# yyb_v2_5_leds.net
KiCad netlist of a schematic drawn in Altium Designer
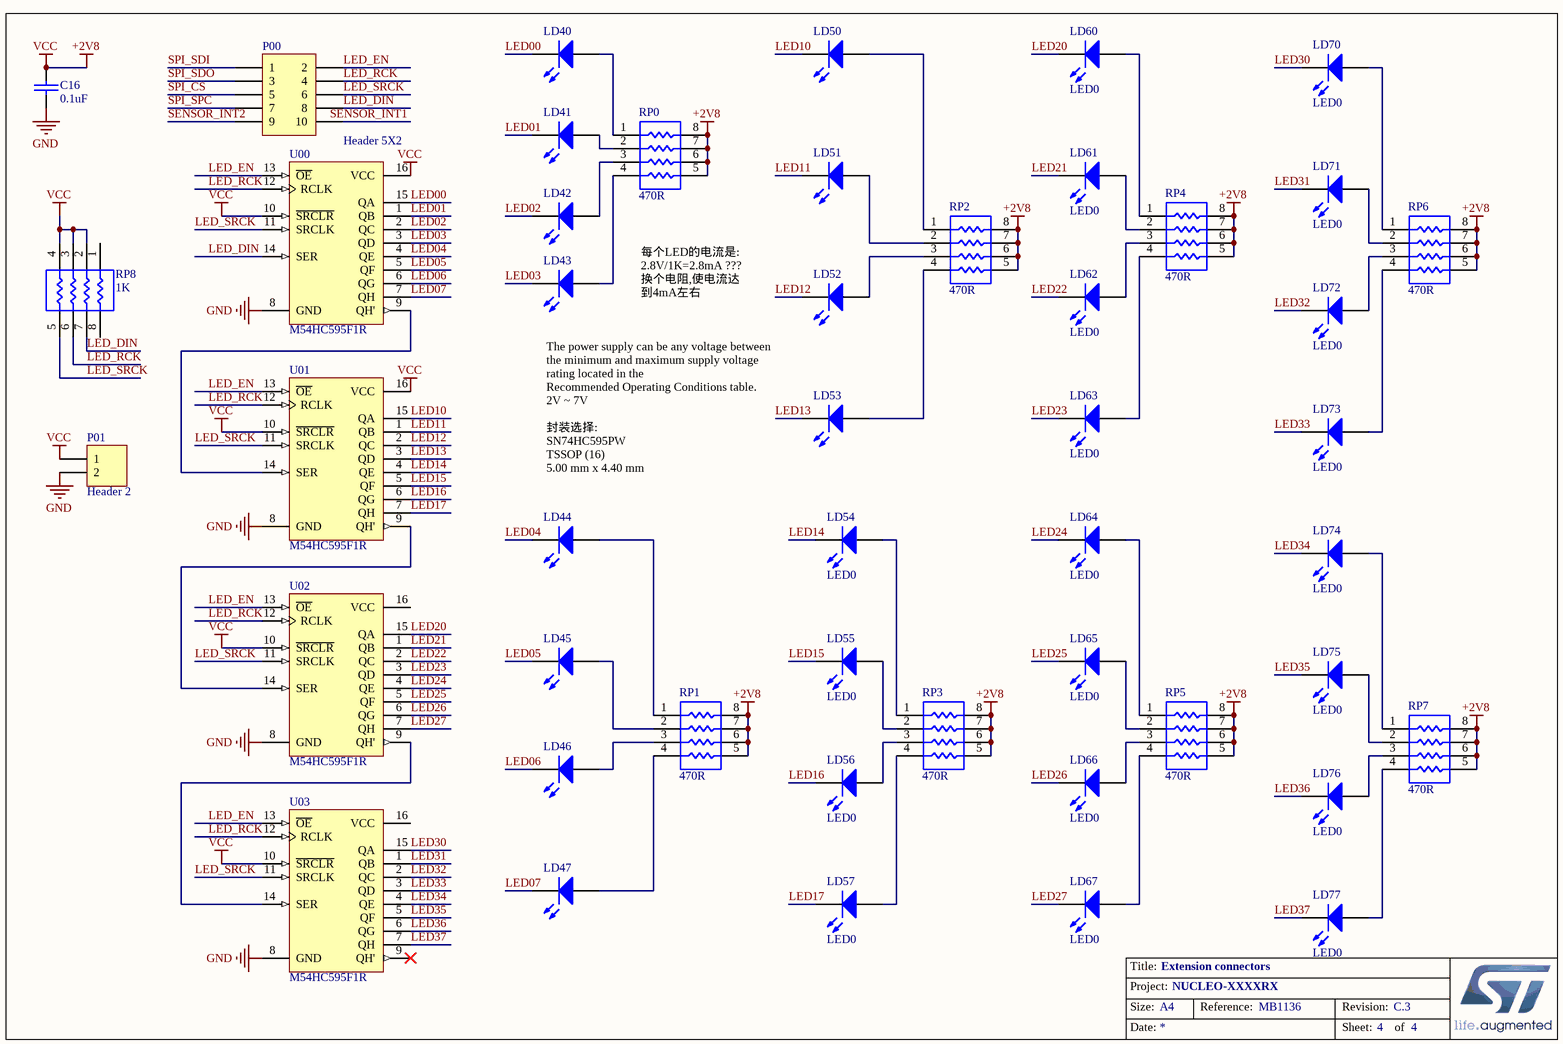
[diagram p0: yyb_v2.5_leds.SchDoc]

(export (version "E")
  (design (tool "Eeschema 10.0.6"))
  (components
    (comp (ref "C16")
      (value "0.1uF")
      (footprint "0603C")
      (description "Capacitor")
      (libsource (lib "*") (part "CAP"))
    )
    (comp (ref "LD40")
      (value "LED0")
      (footprint "LED5")
      (description "Typical INFRARED GaAs LED")
      (fields (field (name "PUBLISHER") "Altium Limited"))
      (libsource (lib "Miscellaneous Devices") (part "LED0"))
    )
    (comp (ref "LD41")
      (value "LED0")
      (footprint "LED5")
      (description "Typical INFRARED GaAs LED")
      (fields (field (name "PUBLISHER") "Altium Limited"))
      (libsource (lib "Miscellaneous Devices") (part "LED0"))
    )
    (comp (ref "LD42")
      (value "LED0")
      (footprint "LED5")
      (description "Typical INFRARED GaAs LED")
      (fields (field (name "PUBLISHER") "Altium Limited"))
      (libsource (lib "Miscellaneous Devices") (part "LED0"))
    )
    (comp (ref "LD43")
      (value "LED0")
      (footprint "LED5")
      (description "Typical INFRARED GaAs LED")
      (fields (field (name "PUBLISHER") "Altium Limited"))
      (libsource (lib "Miscellaneous Devices") (part "LED0"))
    )
    (comp (ref "LD44")
      (value "LED0")
      (footprint "LED5")
      (description "Typical INFRARED GaAs LED")
      (fields (field (name "PUBLISHER") "Altium Limited"))
      (libsource (lib "Miscellaneous Devices") (part "LED0"))
    )
    (comp (ref "LD45")
      (value "LED0")
      (footprint "LED5")
      (description "Typical INFRARED GaAs LED")
      (fields (field (name "PUBLISHER") "Altium Limited"))
      (libsource (lib "Miscellaneous Devices") (part "LED0"))
    )
    (comp (ref "LD46")
      (value "LED0")
      (footprint "LED5")
      (description "Typical INFRARED GaAs LED")
      (fields (field (name "PUBLISHER") "Altium Limited"))
      (libsource (lib "Miscellaneous Devices") (part "LED0"))
    )
    (comp (ref "LD47")
      (value "LED0")
      (footprint "LED5")
      (description "Typical INFRARED GaAs LED")
      (fields (field (name "PUBLISHER") "Altium Limited"))
      (libsource (lib "Miscellaneous Devices") (part "LED0"))
    )
    (comp (ref "LD50")
      (value "LED0")
      (footprint "LED5")
      (description "Typical INFRARED GaAs LED")
      (fields (field (name "PUBLISHER") "Altium Limited"))
      (libsource (lib "Miscellaneous Devices") (part "LED0"))
    )
    (comp (ref "LD51")
      (value "LED0")
      (footprint "LED5")
      (description "Typical INFRARED GaAs LED")
      (fields (field (name "PUBLISHER") "Altium Limited"))
      (libsource (lib "Miscellaneous Devices") (part "LED0"))
    )
    (comp (ref "LD52")
      (value "LED0")
      (footprint "LED5")
      (description "Typical INFRARED GaAs LED")
      (fields (field (name "PUBLISHER") "Altium Limited"))
      (libsource (lib "Miscellaneous Devices") (part "LED0"))
    )
    (comp (ref "LD53")
      (value "LED0")
      (footprint "LED5")
      (description "Typical INFRARED GaAs LED")
      (fields (field (name "PUBLISHER") "Altium Limited"))
      (libsource (lib "Miscellaneous Devices") (part "LED0"))
    )
    (comp (ref "LD54")
      (value "LED0")
      (footprint "LED5")
      (description "Typical INFRARED GaAs LED")
      (fields (field (name "PUBLISHER") "Altium Limited"))
      (libsource (lib "Miscellaneous Devices") (part "LED0"))
    )
    (comp (ref "LD55")
      (value "LED0")
      (footprint "LED5")
      (description "Typical INFRARED GaAs LED")
      (fields (field (name "PUBLISHER") "Altium Limited"))
      (libsource (lib "Miscellaneous Devices") (part "LED0"))
    )
    (comp (ref "LD56")
      (value "LED0")
      (footprint "LED5")
      (description "Typical INFRARED GaAs LED")
      (fields (field (name "PUBLISHER") "Altium Limited"))
      (libsource (lib "Miscellaneous Devices") (part "LED0"))
    )
    (comp (ref "LD57")
      (value "LED0")
      (footprint "LED5")
      (description "Typical INFRARED GaAs LED")
      (fields (field (name "PUBLISHER") "Altium Limited"))
      (libsource (lib "Miscellaneous Devices") (part "LED0"))
    )
    (comp (ref "LD60")
      (value "LED0")
      (footprint "LED5")
      (description "Typical INFRARED GaAs LED")
      (fields (field (name "PUBLISHER") "Altium Limited"))
      (libsource (lib "Miscellaneous Devices") (part "LED0"))
    )
    (comp (ref "LD61")
      (value "LED0")
      (footprint "LED5")
      (description "Typical INFRARED GaAs LED")
      (fields (field (name "PUBLISHER") "Altium Limited"))
      (libsource (lib "Miscellaneous Devices") (part "LED0"))
    )
    (comp (ref "LD62")
      (value "LED0")
      (footprint "LED5")
      (description "Typical INFRARED GaAs LED")
      (fields (field (name "PUBLISHER") "Altium Limited"))
      (libsource (lib "Miscellaneous Devices") (part "LED0"))
    )
    (comp (ref "LD63")
      (value "LED0")
      (footprint "LED5")
      (description "Typical INFRARED GaAs LED")
      (fields (field (name "PUBLISHER") "Altium Limited"))
      (libsource (lib "Miscellaneous Devices") (part "LED0"))
    )
    (comp (ref "LD64")
      (value "LED0")
      (footprint "LED5")
      (description "Typical INFRARED GaAs LED")
      (fields (field (name "PUBLISHER") "Altium Limited"))
      (libsource (lib "Miscellaneous Devices") (part "LED0"))
    )
    (comp (ref "LD65")
      (value "LED0")
      (footprint "LED5")
      (description "Typical INFRARED GaAs LED")
      (fields (field (name "PUBLISHER") "Altium Limited"))
      (libsource (lib "Miscellaneous Devices") (part "LED0"))
    )
    (comp (ref "LD66")
      (value "LED0")
      (footprint "LED5")
      (description "Typical INFRARED GaAs LED")
      (fields (field (name "PUBLISHER") "Altium Limited"))
      (libsource (lib "Miscellaneous Devices") (part "LED0"))
    )
    (comp (ref "LD67")
      (value "LED0")
      (footprint "LED5")
      (description "Typical INFRARED GaAs LED")
      (fields (field (name "PUBLISHER") "Altium Limited"))
      (libsource (lib "Miscellaneous Devices") (part "LED0"))
    )
    (comp (ref "LD70")
      (value "LED0")
      (footprint "LED5")
      (description "Typical INFRARED GaAs LED")
      (fields (field (name "PUBLISHER") "Altium Limited"))
      (libsource (lib "Miscellaneous Devices") (part "LED0"))
    )
    (comp (ref "LD71")
      (value "LED0")
      (footprint "LED5")
      (description "Typical INFRARED GaAs LED")
      (fields (field (name "PUBLISHER") "Altium Limited"))
      (libsource (lib "Miscellaneous Devices") (part "LED0"))
    )
    (comp (ref "LD72")
      (value "LED0")
      (footprint "LED5")
      (description "Typical INFRARED GaAs LED")
      (fields (field (name "PUBLISHER") "Altium Limited"))
      (libsource (lib "Miscellaneous Devices") (part "LED0"))
    )
    (comp (ref "LD73")
      (value "LED0")
      (footprint "LED5")
      (description "Typical INFRARED GaAs LED")
      (fields (field (name "PUBLISHER") "Altium Limited"))
      (libsource (lib "Miscellaneous Devices") (part "LED0"))
    )
    (comp (ref "LD74")
      (value "LED0")
      (footprint "LED5")
      (description "Typical INFRARED GaAs LED")
      (fields (field (name "PUBLISHER") "Altium Limited"))
      (libsource (lib "Miscellaneous Devices") (part "LED0"))
    )
    (comp (ref "LD75")
      (value "LED0")
      (footprint "LED5")
      (description "Typical INFRARED GaAs LED")
      (fields (field (name "PUBLISHER") "Altium Limited"))
      (libsource (lib "Miscellaneous Devices") (part "LED0"))
    )
    (comp (ref "LD76")
      (value "LED0")
      (footprint "LED5")
      (description "Typical INFRARED GaAs LED")
      (fields (field (name "PUBLISHER") "Altium Limited"))
      (libsource (lib "Miscellaneous Devices") (part "LED0"))
    )
    (comp (ref "LD77")
      (value "LED0")
      (footprint "LED5")
      (description "Typical INFRARED GaAs LED")
      (fields (field (name "PUBLISHER") "Altium Limited"))
      (libsource (lib "Miscellaneous Devices") (part "LED0"))
    )
    (comp (ref "P00")
      (value "Header 5X2")
      (footprint "HDR2X5")
      (description "Header, 5-Pin, Dual row")
      (fields (field (name "PUBLISHER") "Altium Limited"))
      (libsource (lib "Miscellaneous Connectors") (part "Header 5X2"))
    )
    (comp (ref "P01")
      (value "Header 2")
      (footprint "HDR1X2")
      (description "Header, 2-Pin")
      (fields (field (name "PUBLISHER") "Altium Limited"))
      (libsource (lib "Miscellaneous Connectors") (part "Header 2"))
    )
    (comp (ref "RP0") (value "470R") (footprint "4P8") (libsource (lib "*") (part "RESPACK3_1")))
    (comp (ref "RP1") (value "470R") (footprint "4P8") (libsource (lib "*") (part "RESPACK3_1")))
    (comp (ref "RP2") (value "470R") (footprint "4P8") (libsource (lib "*") (part "RESPACK3_1")))
    (comp (ref "RP3") (value "470R") (footprint "4P8") (libsource (lib "*") (part "RESPACK3_1")))
    (comp (ref "RP4") (value "470R") (footprint "4P8") (libsource (lib "*") (part "RESPACK3_1")))
    (comp (ref "RP5") (value "470R") (footprint "4P8") (libsource (lib "*") (part "RESPACK3_1")))
    (comp (ref "RP6") (value "470R") (footprint "4P8") (libsource (lib "*") (part "RESPACK3_1")))
    (comp (ref "RP7") (value "470R") (footprint "4P8") (libsource (lib "*") (part "RESPACK3_1")))
    (comp (ref "RP8") (value "1K") (footprint "4P8") (libsource (lib "*") (part "RESPACK3_1")))
    (comp (ref "U00")
      (value "M54HC595F1R")
      (footprint "DIP16")
      (description "8 Bit Shift Register with Output Latches (3 STATE)")
      (fields (field (name "PUBLISHER") "Altium Limited"))
      (libsource (lib "ST Logic Register") (part "M54HC595F1R"))
    )
    (comp (ref "U01")
      (value "M54HC595F1R")
      (footprint "DIP16")
      (description "8 Bit Shift Register with Output Latches (3 STATE)")
      (fields (field (name "PUBLISHER") "Altium Limited"))
      (libsource (lib "ST Logic Register") (part "M54HC595F1R"))
    )
    (comp (ref "U02")
      (value "M54HC595F1R")
      (footprint "DIP16")
      (description "8 Bit Shift Register with Output Latches (3 STATE)")
      (fields (field (name "PUBLISHER") "Altium Limited"))
      (libsource (lib "ST Logic Register") (part "M54HC595F1R"))
    )
    (comp (ref "U03")
      (value "M54HC595F1R")
      (footprint "DIP16")
      (description "8 Bit Shift Register with Output Latches (3 STATE)")
      (fields (field (name "PUBLISHER") "Altium Limited"))
      (libsource (lib "ST Logic Register") (part "M54HC595F1R"))
    )
  )
  (nets
    (net (code "1") (name "+2V8") (class "Default")
      (node (ref "C16") (pin "1") (pinfunction "1_1") (pintype "passive"))
      (node (ref "P01") (pin "1") (pinfunction "1_1") (pintype "passive"))
      (node (ref "RP0") (pin "5") (pinfunction "5_5") (pintype "passive"))
      (node (ref "RP0") (pin "6") (pinfunction "6_6") (pintype "passive"))
      (node (ref "RP0") (pin "7") (pinfunction "7_7") (pintype "passive"))
      (node (ref "RP0") (pin "8") (pinfunction "8_8") (pintype "passive"))
      (node (ref "RP1") (pin "5") (pinfunction "5_5") (pintype "passive"))
      (node (ref "RP1") (pin "6") (pinfunction "6_6") (pintype "passive"))
      (node (ref "RP1") (pin "7") (pinfunction "7_7") (pintype "passive"))
      (node (ref "RP1") (pin "8") (pinfunction "8_8") (pintype "passive"))
      (node (ref "RP2") (pin "5") (pinfunction "5_5") (pintype "passive"))
      (node (ref "RP2") (pin "6") (pinfunction "6_6") (pintype "passive"))
      (node (ref "RP2") (pin "7") (pinfunction "7_7") (pintype "passive"))
      (node (ref "RP2") (pin "8") (pinfunction "8_8") (pintype "passive"))
      (node (ref "RP3") (pin "5") (pinfunction "5_5") (pintype "passive"))
      (node (ref "RP3") (pin "6") (pinfunction "6_6") (pintype "passive"))
      (node (ref "RP3") (pin "7") (pinfunction "7_7") (pintype "passive"))
      (node (ref "RP3") (pin "8") (pinfunction "8_8") (pintype "passive"))
      (node (ref "RP4") (pin "5") (pinfunction "5_5") (pintype "passive"))
      (node (ref "RP4") (pin "6") (pinfunction "6_6") (pintype "passive"))
      (node (ref "RP4") (pin "7") (pinfunction "7_7") (pintype "passive"))
      (node (ref "RP4") (pin "8") (pinfunction "8_8") (pintype "passive"))
      (node (ref "RP5") (pin "5") (pinfunction "5_5") (pintype "passive"))
      (node (ref "RP5") (pin "6") (pinfunction "6_6") (pintype "passive"))
      (node (ref "RP5") (pin "7") (pinfunction "7_7") (pintype "passive"))
      (node (ref "RP5") (pin "8") (pinfunction "8_8") (pintype "passive"))
      (node (ref "RP6") (pin "5") (pinfunction "5_5") (pintype "passive"))
      (node (ref "RP6") (pin "6") (pinfunction "6_6") (pintype "passive"))
      (node (ref "RP6") (pin "7") (pinfunction "7_7") (pintype "passive"))
      (node (ref "RP6") (pin "8") (pinfunction "8_8") (pintype "passive"))
      (node (ref "RP7") (pin "5") (pinfunction "5_5") (pintype "passive"))
      (node (ref "RP7") (pin "6") (pinfunction "6_6") (pintype "passive"))
      (node (ref "RP7") (pin "7") (pinfunction "7_7") (pintype "passive"))
      (node (ref "RP7") (pin "8") (pinfunction "8_8") (pintype "passive"))
      (node (ref "RP8") (pin "2") (pinfunction "2_2") (pintype "passive"))
      (node (ref "RP8") (pin "3") (pinfunction "3_3") (pintype "passive"))
      (node (ref "RP8") (pin "4") (pinfunction "4_4") (pintype "passive"))
      (node (ref "U00") (pin "10") (pinfunction "~{SRCLR}_10") (pintype "input"))
      (node (ref "U00") (pin "16") (pinfunction "VCC_16") (pintype "power_in"))
      (node (ref "U01") (pin "10") (pinfunction "~{SRCLR}_10") (pintype "input"))
      (node (ref "U01") (pin "16") (pinfunction "VCC_16") (pintype "power_in"))
      (node (ref "U02") (pin "10") (pinfunction "~{SRCLR}_10") (pintype "input"))
      (node (ref "U03") (pin "10") (pinfunction "~{SRCLR}_10") (pintype "input"))
    )
    (net (code "2") (name "/LED00") (class "Default")
      (node (ref "LD40") (pin "2") (pinfunction "K_2") (pintype "passive"))
      (node (ref "U00") (pin "15") (pinfunction "QA_15") (pintype "tri_state"))
    )
    (net (code "3") (name "/LED01") (class "Default")
      (node (ref "LD41") (pin "2") (pinfunction "K_2") (pintype "passive"))
      (node (ref "U00") (pin "1") (pinfunction "QB_1") (pintype "tri_state"))
    )
    (net (code "4") (name "/LED02") (class "Default")
      (node (ref "LD42") (pin "2") (pinfunction "K_2") (pintype "passive"))
      (node (ref "U00") (pin "2") (pinfunction "QC_2") (pintype "tri_state"))
    )
    (net (code "5") (name "/LED03") (class "Default")
      (node (ref "LD43") (pin "2") (pinfunction "K_2") (pintype "passive"))
      (node (ref "U00") (pin "3") (pinfunction "QD_3") (pintype "tri_state"))
    )
    (net (code "6") (name "/LED04") (class "Default")
      (node (ref "LD44") (pin "2") (pinfunction "K_2") (pintype "passive"))
      (node (ref "U00") (pin "4") (pinfunction "QE_4") (pintype "tri_state"))
    )
    (net (code "7") (name "/LED05") (class "Default")
      (node (ref "LD45") (pin "2") (pinfunction "K_2") (pintype "passive"))
      (node (ref "U00") (pin "5") (pinfunction "QF_5") (pintype "tri_state"))
    )
    (net (code "8") (name "/LED06") (class "Default")
      (node (ref "LD46") (pin "2") (pinfunction "K_2") (pintype "passive"))
      (node (ref "U00") (pin "6") (pinfunction "QG_6") (pintype "tri_state"))
    )
    (net (code "9") (name "/LED07") (class "Default")
      (node (ref "LD47") (pin "2") (pinfunction "K_2") (pintype "passive"))
      (node (ref "U00") (pin "7") (pinfunction "QH_7") (pintype "tri_state"))
    )
    (net (code "10") (name "/LED10") (class "Default")
      (node (ref "LD50") (pin "2") (pinfunction "K_2") (pintype "passive"))
      (node (ref "U01") (pin "15") (pinfunction "QA_15") (pintype "tri_state"))
    )
    (net (code "11") (name "/LED11") (class "Default")
      (node (ref "LD51") (pin "2") (pinfunction "K_2") (pintype "passive"))
      (node (ref "U01") (pin "1") (pinfunction "QB_1") (pintype "tri_state"))
    )
    (net (code "12") (name "/LED12") (class "Default")
      (node (ref "LD52") (pin "2") (pinfunction "K_2") (pintype "passive"))
      (node (ref "U01") (pin "2") (pinfunction "QC_2") (pintype "tri_state"))
    )
    (net (code "13") (name "/LED13") (class "Default")
      (node (ref "LD53") (pin "2") (pinfunction "K_2") (pintype "passive"))
      (node (ref "U01") (pin "3") (pinfunction "QD_3") (pintype "tri_state"))
    )
    (net (code "14") (name "/LED14") (class "Default")
      (node (ref "LD54") (pin "2") (pinfunction "K_2") (pintype "passive"))
      (node (ref "U01") (pin "4") (pinfunction "QE_4") (pintype "tri_state"))
    )
    (net (code "15") (name "/LED15") (class "Default")
      (node (ref "LD55") (pin "2") (pinfunction "K_2") (pintype "passive"))
      (node (ref "U01") (pin "5") (pinfunction "QF_5") (pintype "tri_state"))
    )
    (net (code "16") (name "/LED16") (class "Default")
      (node (ref "LD56") (pin "2") (pinfunction "K_2") (pintype "passive"))
      (node (ref "U01") (pin "6") (pinfunction "QG_6") (pintype "tri_state"))
    )
    (net (code "17") (name "/LED17") (class "Default")
      (node (ref "LD57") (pin "2") (pinfunction "K_2") (pintype "passive"))
      (node (ref "U01") (pin "7") (pinfunction "QH_7") (pintype "tri_state"))
    )
    (net (code "18") (name "/LED20") (class "Default")
      (node (ref "LD60") (pin "2") (pinfunction "K_2") (pintype "passive"))
      (node (ref "U02") (pin "15") (pinfunction "QA_15") (pintype "tri_state"))
    )
    (net (code "19") (name "/LED21") (class "Default")
      (node (ref "LD61") (pin "2") (pinfunction "K_2") (pintype "passive"))
      (node (ref "U02") (pin "1") (pinfunction "QB_1") (pintype "tri_state"))
    )
    (net (code "20") (name "/LED22") (class "Default")
      (node (ref "LD62") (pin "2") (pinfunction "K_2") (pintype "passive"))
      (node (ref "U02") (pin "2") (pinfunction "QC_2") (pintype "tri_state"))
    )
    (net (code "21") (name "/LED23") (class "Default")
      (node (ref "LD63") (pin "2") (pinfunction "K_2") (pintype "passive"))
      (node (ref "U02") (pin "3") (pinfunction "QD_3") (pintype "tri_state"))
    )
    (net (code "22") (name "/LED24") (class "Default")
      (node (ref "LD64") (pin "2") (pinfunction "K_2") (pintype "passive"))
      (node (ref "U02") (pin "4") (pinfunction "QE_4") (pintype "tri_state"))
    )
    (net (code "23") (name "/LED25") (class "Default")
      (node (ref "LD65") (pin "2") (pinfunction "K_2") (pintype "passive"))
      (node (ref "U02") (pin "5") (pinfunction "QF_5") (pintype "tri_state"))
    )
    (net (code "24") (name "/LED26") (class "Default")
      (node (ref "LD66") (pin "2") (pinfunction "K_2") (pintype "passive"))
      (node (ref "U02") (pin "6") (pinfunction "QG_6") (pintype "tri_state"))
    )
    (net (code "25") (name "/LED27") (class "Default")
      (node (ref "LD67") (pin "2") (pinfunction "K_2") (pintype "passive"))
      (node (ref "U02") (pin "7") (pinfunction "QH_7") (pintype "tri_state"))
    )
    (net (code "26") (name "/LED30") (class "Default")
      (node (ref "LD70") (pin "2") (pinfunction "K_2") (pintype "passive"))
      (node (ref "U03") (pin "15") (pinfunction "QA_15") (pintype "tri_state"))
    )
    (net (code "27") (name "/LED31") (class "Default")
      (node (ref "LD71") (pin "2") (pinfunction "K_2") (pintype "passive"))
      (node (ref "U03") (pin "1") (pinfunction "QB_1") (pintype "tri_state"))
    )
    (net (code "28") (name "/LED32") (class "Default")
      (node (ref "LD72") (pin "2") (pinfunction "K_2") (pintype "passive"))
      (node (ref "U03") (pin "2") (pinfunction "QC_2") (pintype "tri_state"))
    )
    (net (code "29") (name "/LED33") (class "Default")
      (node (ref "LD73") (pin "2") (pinfunction "K_2") (pintype "passive"))
      (node (ref "U03") (pin "3") (pinfunction "QD_3") (pintype "tri_state"))
    )
    (net (code "30") (name "/LED34") (class "Default")
      (node (ref "LD74") (pin "2") (pinfunction "K_2") (pintype "passive"))
      (node (ref "U03") (pin "4") (pinfunction "QE_4") (pintype "tri_state"))
    )
    (net (code "31") (name "/LED35") (class "Default")
      (node (ref "LD75") (pin "2") (pinfunction "K_2") (pintype "passive"))
      (node (ref "U03") (pin "5") (pinfunction "QF_5") (pintype "tri_state"))
    )
    (net (code "32") (name "/LED36") (class "Default")
      (node (ref "LD76") (pin "2") (pinfunction "K_2") (pintype "passive"))
      (node (ref "U03") (pin "6") (pinfunction "QG_6") (pintype "tri_state"))
    )
    (net (code "33") (name "/LED37") (class "Default")
      (node (ref "LD77") (pin "2") (pinfunction "K_2") (pintype "passive"))
      (node (ref "U03") (pin "7") (pinfunction "QH_7") (pintype "tri_state"))
    )
    (net (code "34") (name "/LED_DIN") (class "Default")
      (node (ref "P00") (pin "8") (pinfunction "8_8") (pintype "passive"))
      (node (ref "RP8") (pin "7") (pinfunction "7_7") (pintype "passive"))
      (node (ref "U00") (pin "14") (pinfunction "SER_14") (pintype "input"))
    )
    (net (code "35") (name "/LED_EN") (class "Default")
      (node (ref "P00") (pin "2") (pinfunction "2_2") (pintype "passive"))
      (node (ref "U00") (pin "13") (pinfunction "~{OE}_13") (pintype "input"))
      (node (ref "U01") (pin "13") (pinfunction "~{OE}_13") (pintype "input"))
      (node (ref "U02") (pin "13") (pinfunction "~{OE}_13") (pintype "input"))
      (node (ref "U03") (pin "13") (pinfunction "~{OE}_13") (pintype "input"))
    )
    (net (code "36") (name "/LED_RCK") (class "Default")
      (node (ref "P00") (pin "4") (pinfunction "4_4") (pintype "passive"))
      (node (ref "RP8") (pin "6") (pinfunction "6_6") (pintype "passive"))
      (node (ref "U00") (pin "12") (pinfunction "RCLK_12") (pintype "input"))
      (node (ref "U01") (pin "12") (pinfunction "RCLK_12") (pintype "input"))
      (node (ref "U02") (pin "12") (pinfunction "RCLK_12") (pintype "input"))
      (node (ref "U03") (pin "12") (pinfunction "RCLK_12") (pintype "input"))
    )
    (net (code "37") (name "/LED_SRCK") (class "Default")
      (node (ref "P00") (pin "6") (pinfunction "6_6") (pintype "passive"))
      (node (ref "RP8") (pin "5") (pinfunction "5_5") (pintype "passive"))
      (node (ref "U00") (pin "11") (pinfunction "SRCLK_11") (pintype "input"))
      (node (ref "U01") (pin "11") (pinfunction "SRCLK_11") (pintype "input"))
      (node (ref "U02") (pin "11") (pinfunction "SRCLK_11") (pintype "input"))
      (node (ref "U03") (pin "11") (pinfunction "SRCLK_11") (pintype "input"))
    )
    (net (code "39") (name "/SENSOR_INT2") (class "Default")
      (node (ref "P00") (pin "9") (pinfunction "9_9") (pintype "passive"))
    )
    (net (code "40") (name "/SPI_CS") (class "Default")
      (node (ref "P00") (pin "5") (pinfunction "5_5") (pintype "passive"))
    )
    (net (code "41") (name "/SPI_SDI") (class "Default")
      (node (ref "P00") (pin "1") (pinfunction "1_1") (pintype "passive"))
    )
    (net (code "42") (name "/SPI_SDO") (class "Default")
      (node (ref "P00") (pin "3") (pinfunction "3_3") (pintype "passive"))
    )
    (net (code "43") (name "/SPI_SPC") (class "Default")
      (node (ref "P00") (pin "7") (pinfunction "7_7") (pintype "passive"))
    )
    (net (code "44") (name "GND") (class "Default")
      (node (ref "C16") (pin "2") (pinfunction "2_2") (pintype "passive"))
      (node (ref "P01") (pin "2") (pinfunction "2_2") (pintype "passive"))
      (node (ref "U00") (pin "8") (pinfunction "GND_8") (pintype "power_in"))
      (node (ref "U01") (pin "8") (pinfunction "GND_8") (pintype "power_in"))
      (node (ref "U02") (pin "8") (pinfunction "GND_8") (pintype "power_in"))
      (node (ref "U03") (pin "8") (pinfunction "GND_8") (pintype "power_in"))
    )
    (net (code "45") (name "Net-(LD40-A)") (class "Default")
      (node (ref "LD40") (pin "1") (pinfunction "A_1") (pintype "passive"))
      (node (ref "RP0") (pin "1") (pinfunction "1_1") (pintype "passive"))
    )
    (net (code "46") (name "Net-(LD41-A)") (class "Default")
      (node (ref "LD41") (pin "1") (pinfunction "A_1") (pintype "passive"))
      (node (ref "RP0") (pin "2") (pinfunction "2_2") (pintype "passive"))
    )
    (net (code "47") (name "Net-(LD42-A)") (class "Default")
      (node (ref "LD42") (pin "1") (pinfunction "A_1") (pintype "passive"))
      (node (ref "RP0") (pin "3") (pinfunction "3_3") (pintype "passive"))
    )
    (net (code "48") (name "Net-(LD43-A)") (class "Default")
      (node (ref "LD43") (pin "1") (pinfunction "A_1") (pintype "passive"))
      (node (ref "RP0") (pin "4") (pinfunction "4_4") (pintype "passive"))
    )
    (net (code "49") (name "Net-(LD44-A)") (class "Default")
      (node (ref "LD44") (pin "1") (pinfunction "A_1") (pintype "passive"))
      (node (ref "RP1") (pin "1") (pinfunction "1_1") (pintype "passive"))
    )
    (net (code "50") (name "Net-(LD45-A)") (class "Default")
      (node (ref "LD45") (pin "1") (pinfunction "A_1") (pintype "passive"))
      (node (ref "RP1") (pin "2") (pinfunction "2_2") (pintype "passive"))
    )
    (net (code "51") (name "Net-(LD46-A)") (class "Default")
      (node (ref "LD46") (pin "1") (pinfunction "A_1") (pintype "passive"))
      (node (ref "RP1") (pin "3") (pinfunction "3_3") (pintype "passive"))
    )
    (net (code "52") (name "Net-(LD47-A)") (class "Default")
      (node (ref "LD47") (pin "1") (pinfunction "A_1") (pintype "passive"))
      (node (ref "RP1") (pin "4") (pinfunction "4_4") (pintype "passive"))
    )
    (net (code "53") (name "Net-(LD50-A)") (class "Default")
      (node (ref "LD50") (pin "1") (pinfunction "A_1") (pintype "passive"))
      (node (ref "RP2") (pin "1") (pinfunction "1_1") (pintype "passive"))
    )
    (net (code "54") (name "Net-(LD51-A)") (class "Default")
      (node (ref "LD51") (pin "1") (pinfunction "A_1") (pintype "passive"))
      (node (ref "RP2") (pin "2") (pinfunction "2_2") (pintype "passive"))
    )
    (net (code "55") (name "Net-(LD52-A)") (class "Default")
      (node (ref "LD52") (pin "1") (pinfunction "A_1") (pintype "passive"))
      (node (ref "RP2") (pin "3") (pinfunction "3_3") (pintype "passive"))
    )
    (net (code "56") (name "Net-(LD53-A)") (class "Default")
      (node (ref "LD53") (pin "1") (pinfunction "A_1") (pintype "passive"))
      (node (ref "RP2") (pin "4") (pinfunction "4_4") (pintype "passive"))
    )
    (net (code "57") (name "Net-(LD54-A)") (class "Default")
      (node (ref "LD54") (pin "1") (pinfunction "A_1") (pintype "passive"))
      (node (ref "RP3") (pin "1") (pinfunction "1_1") (pintype "passive"))
    )
    (net (code "58") (name "Net-(LD55-A)") (class "Default")
      (node (ref "LD55") (pin "1") (pinfunction "A_1") (pintype "passive"))
      (node (ref "RP3") (pin "2") (pinfunction "2_2") (pintype "passive"))
    )
    (net (code "59") (name "Net-(LD56-A)") (class "Default")
      (node (ref "LD56") (pin "1") (pinfunction "A_1") (pintype "passive"))
      (node (ref "RP3") (pin "3") (pinfunction "3_3") (pintype "passive"))
    )
    (net (code "60") (name "Net-(LD57-A)") (class "Default")
      (node (ref "LD57") (pin "1") (pinfunction "A_1") (pintype "passive"))
      (node (ref "RP3") (pin "4") (pinfunction "4_4") (pintype "passive"))
    )
    (net (code "61") (name "Net-(LD60-A)") (class "Default")
      (node (ref "LD60") (pin "1") (pinfunction "A_1") (pintype "passive"))
      (node (ref "RP4") (pin "1") (pinfunction "1_1") (pintype "passive"))
    )
    (net (code "62") (name "Net-(LD61-A)") (class "Default")
      (node (ref "LD61") (pin "1") (pinfunction "A_1") (pintype "passive"))
      (node (ref "RP4") (pin "2") (pinfunction "2_2") (pintype "passive"))
    )
    (net (code "63") (name "Net-(LD62-A)") (class "Default")
      (node (ref "LD62") (pin "1") (pinfunction "A_1") (pintype "passive"))
      (node (ref "RP4") (pin "3") (pinfunction "3_3") (pintype "passive"))
    )
    (net (code "64") (name "Net-(LD63-A)") (class "Default")
      (node (ref "LD63") (pin "1") (pinfunction "A_1") (pintype "passive"))
      (node (ref "RP4") (pin "4") (pinfunction "4_4") (pintype "passive"))
    )
    (net (code "65") (name "Net-(LD64-A)") (class "Default")
      (node (ref "LD64") (pin "1") (pinfunction "A_1") (pintype "passive"))
      (node (ref "RP5") (pin "1") (pinfunction "1_1") (pintype "passive"))
    )
    (net (code "66") (name "Net-(LD65-A)") (class "Default")
      (node (ref "LD65") (pin "1") (pinfunction "A_1") (pintype "passive"))
      (node (ref "RP5") (pin "2") (pinfunction "2_2") (pintype "passive"))
    )
    (net (code "67") (name "Net-(LD66-A)") (class "Default")
      (node (ref "LD66") (pin "1") (pinfunction "A_1") (pintype "passive"))
      (node (ref "RP5") (pin "3") (pinfunction "3_3") (pintype "passive"))
    )
    (net (code "68") (name "Net-(LD67-A)") (class "Default")
      (node (ref "LD67") (pin "1") (pinfunction "A_1") (pintype "passive"))
      (node (ref "RP5") (pin "4") (pinfunction "4_4") (pintype "passive"))
    )
    (net (code "69") (name "Net-(LD70-A)") (class "Default")
      (node (ref "LD70") (pin "1") (pinfunction "A_1") (pintype "passive"))
      (node (ref "RP6") (pin "1") (pinfunction "1_1") (pintype "passive"))
    )
    (net (code "70") (name "Net-(LD71-A)") (class "Default")
      (node (ref "LD71") (pin "1") (pinfunction "A_1") (pintype "passive"))
      (node (ref "RP6") (pin "2") (pinfunction "2_2") (pintype "passive"))
    )
    (net (code "71") (name "Net-(LD72-A)") (class "Default")
      (node (ref "LD72") (pin "1") (pinfunction "A_1") (pintype "passive"))
      (node (ref "RP6") (pin "3") (pinfunction "3_3") (pintype "passive"))
    )
    (net (code "72") (name "Net-(LD73-A)") (class "Default")
      (node (ref "LD73") (pin "1") (pinfunction "A_1") (pintype "passive"))
      (node (ref "RP6") (pin "4") (pinfunction "4_4") (pintype "passive"))
    )
    (net (code "73") (name "Net-(LD74-A)") (class "Default")
      (node (ref "LD74") (pin "1") (pinfunction "A_1") (pintype "passive"))
      (node (ref "RP7") (pin "1") (pinfunction "1_1") (pintype "passive"))
    )
    (net (code "74") (name "Net-(LD75-A)") (class "Default")
      (node (ref "LD75") (pin "1") (pinfunction "A_1") (pintype "passive"))
      (node (ref "RP7") (pin "2") (pinfunction "2_2") (pintype "passive"))
    )
    (net (code "75") (name "Net-(LD76-A)") (class "Default")
      (node (ref "LD76") (pin "1") (pinfunction "A_1") (pintype "passive"))
      (node (ref "RP7") (pin "3") (pinfunction "3_3") (pintype "passive"))
    )
    (net (code "76") (name "Net-(LD77-A)") (class "Default")
      (node (ref "LD77") (pin "1") (pinfunction "A_1") (pintype "passive"))
      (node (ref "RP7") (pin "4") (pinfunction "4_4") (pintype "passive"))
    )
    (net (code "77") (name "Net-(U00-QH')") (class "Default")
      (node (ref "U00") (pin "9") (pinfunction "QH'_9") (pintype "output"))
      (node (ref "U01") (pin "14") (pinfunction "SER_14") (pintype "input"))
    )
    (net (code "78") (name "Net-(U01-QH')") (class "Default")
      (node (ref "U01") (pin "9") (pinfunction "QH'_9") (pintype "output"))
      (node (ref "U02") (pin "14") (pinfunction "SER_14") (pintype "input"))
    )
    (net (code "79") (name "Net-(U02-QH')") (class "Default")
      (node (ref "U02") (pin "9") (pinfunction "QH'_9") (pintype "output"))
      (node (ref "U03") (pin "14") (pinfunction "SER_14") (pintype "input"))
    )
    (net (code "80") (name "unconnected-(P00-Pad10)") (class "Default")
      (node (ref "P00") (pin "10") (pinfunction "10_10") (pintype "passive"))
    )
    (net (code "81") (name "unconnected-(RP8-Pad1)") (class "Default")
      (node (ref "RP8") (pin "1") (pinfunction "1_1") (pintype "passive"))
    )
    (net (code "82") (name "unconnected-(RP8-Pad8)") (class "Default")
      (node (ref "RP8") (pin "8") (pinfunction "8_8") (pintype "passive"))
    )
    (net (code "83") (name "unconnected-(U02-VCC-Pad16)") (class "Default")
      (node (ref "U02") (pin "16") (pinfunction "VCC_16") (pintype "power_in"))
    )
    (net (code "84") (name "unconnected-(U03-QH'-Pad9)") (class "Default")
      (node (ref "U03") (pin "9") (pinfunction "QH'_9") (pintype "output+no_connect"))
    )
    (net (code "85") (name "unconnected-(U03-VCC-Pad16)") (class "Default")
      (node (ref "U03") (pin "16") (pinfunction "VCC_16") (pintype "power_in"))
    )
  )
)
